# 03_Power_Delivery.net
KiCad netlist of a schematic drawn in Altium Designer
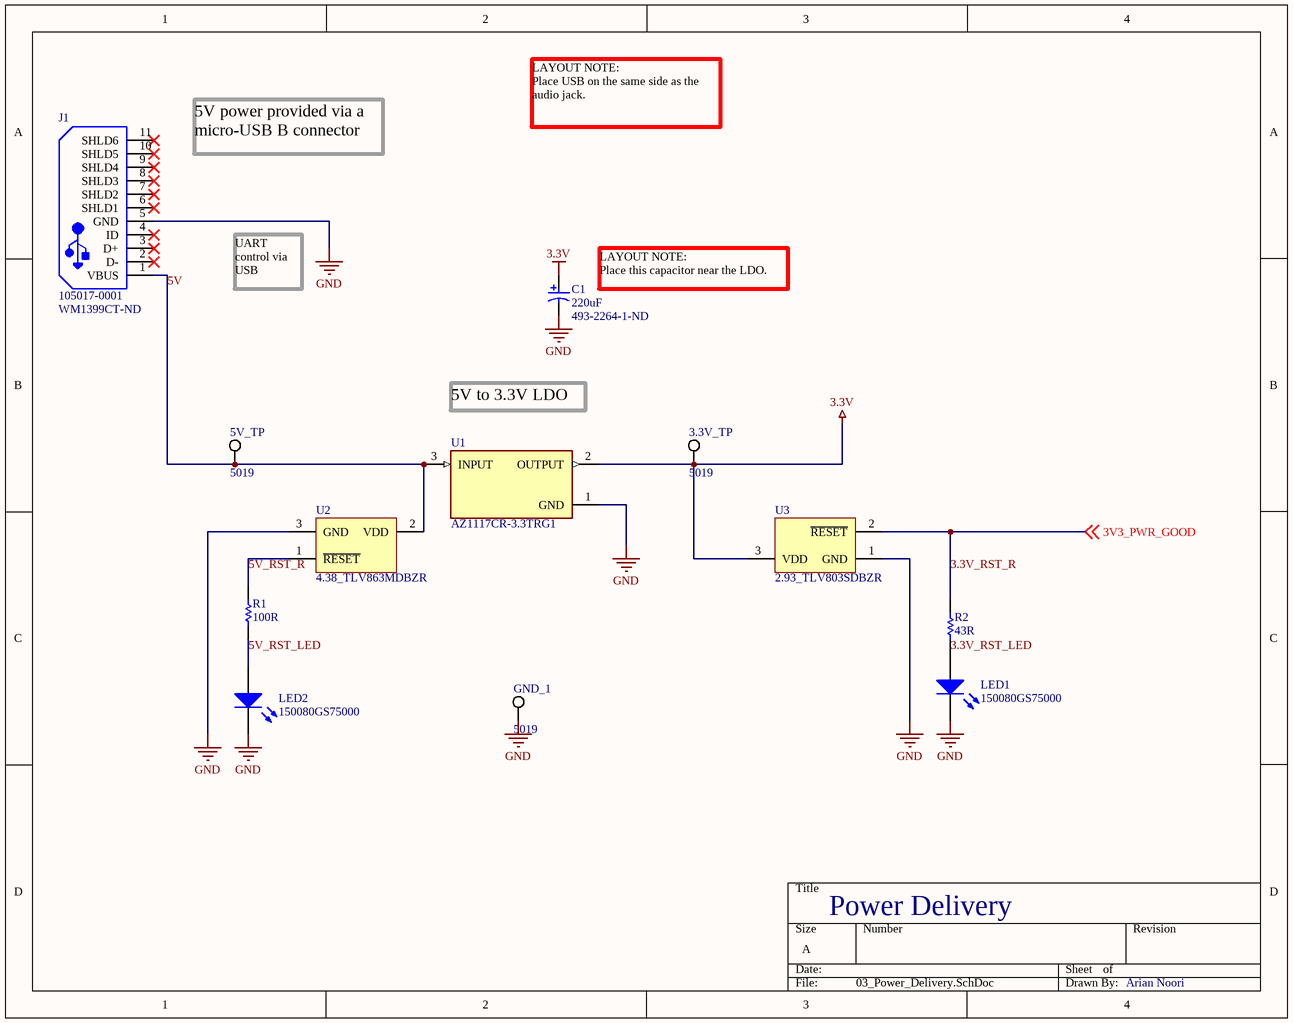
[diagram p0: 03_Power_Delivery.SchDoc]

(export (version "E")
  (design (tool "Eeschema 10.0.6"))
  (components
    (comp (ref "3.3V_TP")
      (value "5019")
      (footprint "KSTN-5019_V")
      (description "Test Point, 1 Position SMD, RoHS, Tape and Reel")
      (fields (field (name "MANUFACTURER") "Keystone Electronics"))
      (libsource (lib "Altium Content Vault") (part "TESTPOINT_WHITE"))
    )
    (comp (ref "5V_TP")
      (value "5019")
      (footprint "KSTN-5019_V")
      (description "Test Point, 1 Position SMD, RoHS, Tape and Reel")
      (fields (field (name "MANUFACTURER") "Keystone Electronics"))
      (libsource (lib "Altium Content Vault") (part "TESTPOINT_WHITE"))
    )
    (comp (ref "C1")
      (value "220uF")
      (footprint "NIC-CAPA2-6.3X7.7_V")
      (description "Aluminum Electrolytic Capacitor, 220uF 16 V, UD Series 2000h 6.3 (Dia.) x 7.7mm")
      (fields
        (field (name "PARTNUMBER") "UUD1C221MCL1GS")
        (field (name "MANUFACTURER") "Nichicon")
        (field (name "SUPPLIER PART NUMBER 1") "493-2264-1-ND")
      )
      (libsource (lib "Altium Content Vault") (part "NIC-CAP-P-2"))
    )
    (comp (ref "GND_1")
      (value "5019")
      (footprint "KSTN-5019_V")
      (description "Test Point, 1 Position SMD, RoHS, Tape and Reel")
      (fields (field (name "MANUFACTURER") "Keystone Electronics"))
      (libsource (lib "Altium Content Vault") (part "TESTPOINT_WHITE"))
    )
    (comp (ref "J1")
      (value "105017-0001")
      (footprint "USB-MICRO-B_V")
      (fields
        (field (name "MANUFACTURER") "Molex")
        (field (name "SUPPLIER PART NUMBER 1") "WM1399CT-ND")
        (field (name "MANUFACTURER PART NUMBER") "1050170001")
      )
      (libsource (lib "Altium Content Vault") (part "USB-5-6SHLD"))
    )
    (comp (ref "LED1")
      (value "150080GS75000")
      (footprint "0805_A")
      (description "SMD mono-color Chip LED, WL-SMCW, Green")
      (fields (field (name "MANUFACTURER") "Wuerth Elektronik"))
      (libsource (lib "Altium Content Vault") (part "WE-LED_K1A2-2"))
    )
    (comp (ref "LED2")
      (value "150080GS75000")
      (footprint "0805_A")
      (description "SMD mono-color Chip LED, WL-SMCW, Green")
      (fields (field (name "MANUFACTURER") "Wuerth Elektronik"))
      (libsource (lib "Altium Content Vault") (part "WE-LED_K1A2-2"))
    )
    (comp (ref "R1")
      (value "100R")
      (footprint "RESC2013X60X35ML10T20")
      (description "Chip Resistor, 100 Ohm, +/-1%, 0.125 W, -55 to 155 degC, 0805 (2012 Metric), RoHS, Tape and Reel")
      (fields (field (name "TOLERANCE") "1%") (field (name "MANUFACTURER") "Yageo"))
      (libsource (lib "Altium Content Vault") (part "RES-2"))
    )
    (comp (ref "R2")
      (value "43R")
      (footprint "RESC2013X60X35LL10T20")
      (description "RES 43 OHM 1/8W .5% SMD 0805")
      (fields (field (name "PART NUMBER") "RC0805JR-0743RL") (field (name "MANUFACTURER") "Yageo"))
      (libsource (lib "Altium Content Vault") (part "RES"))
    )
    (comp (ref "U1")
      (value "AZ1117CR-3.3TRG1")
      (footprint "FP-SOT89-MFG")
      (description "IC REG LINEAR 3.3V 800MA SOT89")
      (fields
        (field (name "OCTOPART") "https://octopart.com/az1117cr-3.3trg1-diodes+inc.-30954805")
        (field (name "MANUFACTURER") "Diodes Inc.")
      )
      (libsource (lib "Altium Content Vault") (part "80dc4d5e0c5bf011f486f511683fde3"))
    )
    (comp (ref "U2")
      (value "4.38_TLV863MDBZR")
      (footprint "DBZ0003A_N")
      (fields (field (name "MANUFACTURER") "Texas Instruments") (field (name "PARTNUMBER") "TLV863MDBZR"))
      (libsource (lib "Altium Content Vault") (part "TI-TLV863MDBZ3"))
    )
    (comp (ref "U3")
      (value "2.93_TLV803SDBZR")
      (footprint "DBZ0003A_M")
      (fields (field (name "MANUFACTURER") "Texas Instruments") (field (name "PARTNUMBER") "TLV803SDBZR"))
      (libsource (lib "Altium Content Vault") (part "TI-TLV803SDBZ3"))
    )
  )
  (nets
    (net (code "1") (name "/3.3V_RST_LED") (class "Default")
      (node (ref "LED1") (pin "2") (pinfunction "A_2") (pintype "passive"))
      (node (ref "R2") (pin "1") (pinfunction "1_1") (pintype "passive"))
    )
    (net (code "2") (name "/5V") (class "Default")
      (node (ref "5V_TP") (pin "1") (pinfunction "1_1") (pintype "passive"))
      (node (ref "J1") (pin "1") (pinfunction "VBUS_1") (pintype "passive"))
      (node (ref "U1") (pin "3") (pinfunction "INPUT_3") (pintype "input"))
      (node (ref "U2") (pin "2") (pinfunction "VDD_2") (pintype "power_in"))
    )
    (net (code "3") (name "/5V_RST_LED") (class "Default")
      (node (ref "LED2") (pin "2") (pinfunction "A_2") (pintype "passive"))
      (node (ref "R1") (pin "1") (pinfunction "1_1") (pintype "passive"))
    )
    (net (code "4") (name "/5V_RST_R") (class "Default")
      (node (ref "R1") (pin "2") (pinfunction "2_2") (pintype "passive"))
      (node (ref "U2") (pin "1") (pinfunction "~{RESET}_1") (pintype "open_collector"))
    )
    (net (code "5") (name "3.3V") (class "Default")
      (node (ref "3.3V_TP") (pin "1") (pinfunction "1_1") (pintype "passive"))
      (node (ref "C1") (pin "1") (pinfunction "1_1") (pintype "passive"))
      (node (ref "U1") (pin "2") (pinfunction "OUTPUT_2") (pintype "output"))
      (node (ref "U3") (pin "3") (pinfunction "VDD_3") (pintype "power_in"))
    )
    (net (code "6") (name "3V3_PWR_GOOD") (class "Default")
      (node (ref "R2") (pin "2") (pinfunction "2_2") (pintype "passive"))
      (node (ref "U3") (pin "2") (pinfunction "~{RESET}_2") (pintype "open_collector"))
    )
    (net (code "7") (name "GND") (class "Default")
      (node (ref "C1") (pin "2") (pinfunction "2_2") (pintype "passive"))
      (node (ref "GND_1") (pin "1") (pinfunction "1_1") (pintype "passive"))
      (node (ref "J1") (pin "5") (pinfunction "GND_5") (pintype "passive"))
      (node (ref "LED1") (pin "1") (pinfunction "K_1") (pintype "passive"))
      (node (ref "LED2") (pin "1") (pinfunction "K_1") (pintype "passive"))
      (node (ref "U1") (pin "1") (pinfunction "GND_1") (pintype "power_in"))
      (node (ref "U2") (pin "3") (pinfunction "GND_3") (pintype "power_in"))
      (node (ref "U3") (pin "1") (pinfunction "GND_1") (pintype "power_in"))
    )
    (net (code "8") (name "unconnected-(J1-D+-Pad3)") (class "Default")
      (node (ref "J1") (pin "3") (pinfunction "D+_3") (pintype "passive+no_connect"))
    )
    (net (code "9") (name "unconnected-(J1-D--Pad2)") (class "Default")
      (node (ref "J1") (pin "2") (pinfunction "D-_2") (pintype "passive+no_connect"))
    )
    (net (code "10") (name "unconnected-(J1-ID-Pad4)") (class "Default")
      (node (ref "J1") (pin "4") (pinfunction "ID_4") (pintype "passive+no_connect"))
    )
    (net (code "11") (name "unconnected-(J1-SHLD1-Pad6)") (class "Default")
      (node (ref "J1") (pin "6") (pinfunction "SHLD1_6") (pintype "passive+no_connect"))
    )
    (net (code "12") (name "unconnected-(J1-SHLD2-Pad7)") (class "Default")
      (node (ref "J1") (pin "7") (pinfunction "SHLD2_7") (pintype "passive+no_connect"))
    )
    (net (code "13") (name "unconnected-(J1-SHLD3-Pad8)") (class "Default")
      (node (ref "J1") (pin "8") (pinfunction "SHLD3_8") (pintype "passive+no_connect"))
    )
    (net (code "14") (name "unconnected-(J1-SHLD4-Pad9)") (class "Default")
      (node (ref "J1") (pin "9") (pinfunction "SHLD4_9") (pintype "passive+no_connect"))
    )
    (net (code "15") (name "unconnected-(J1-SHLD5-Pad10)") (class "Default")
      (node (ref "J1") (pin "10") (pinfunction "SHLD5_10") (pintype "passive+no_connect"))
    )
    (net (code "16") (name "unconnected-(J1-SHLD6-Pad11)") (class "Default")
      (node (ref "J1") (pin "11") (pinfunction "SHLD6_11") (pintype "passive+no_connect"))
    )
  )
)
